# ProPrj_wildCat_2025-03-28.net
KiCad netlist of a schematic drawn in EasyEDA Pro
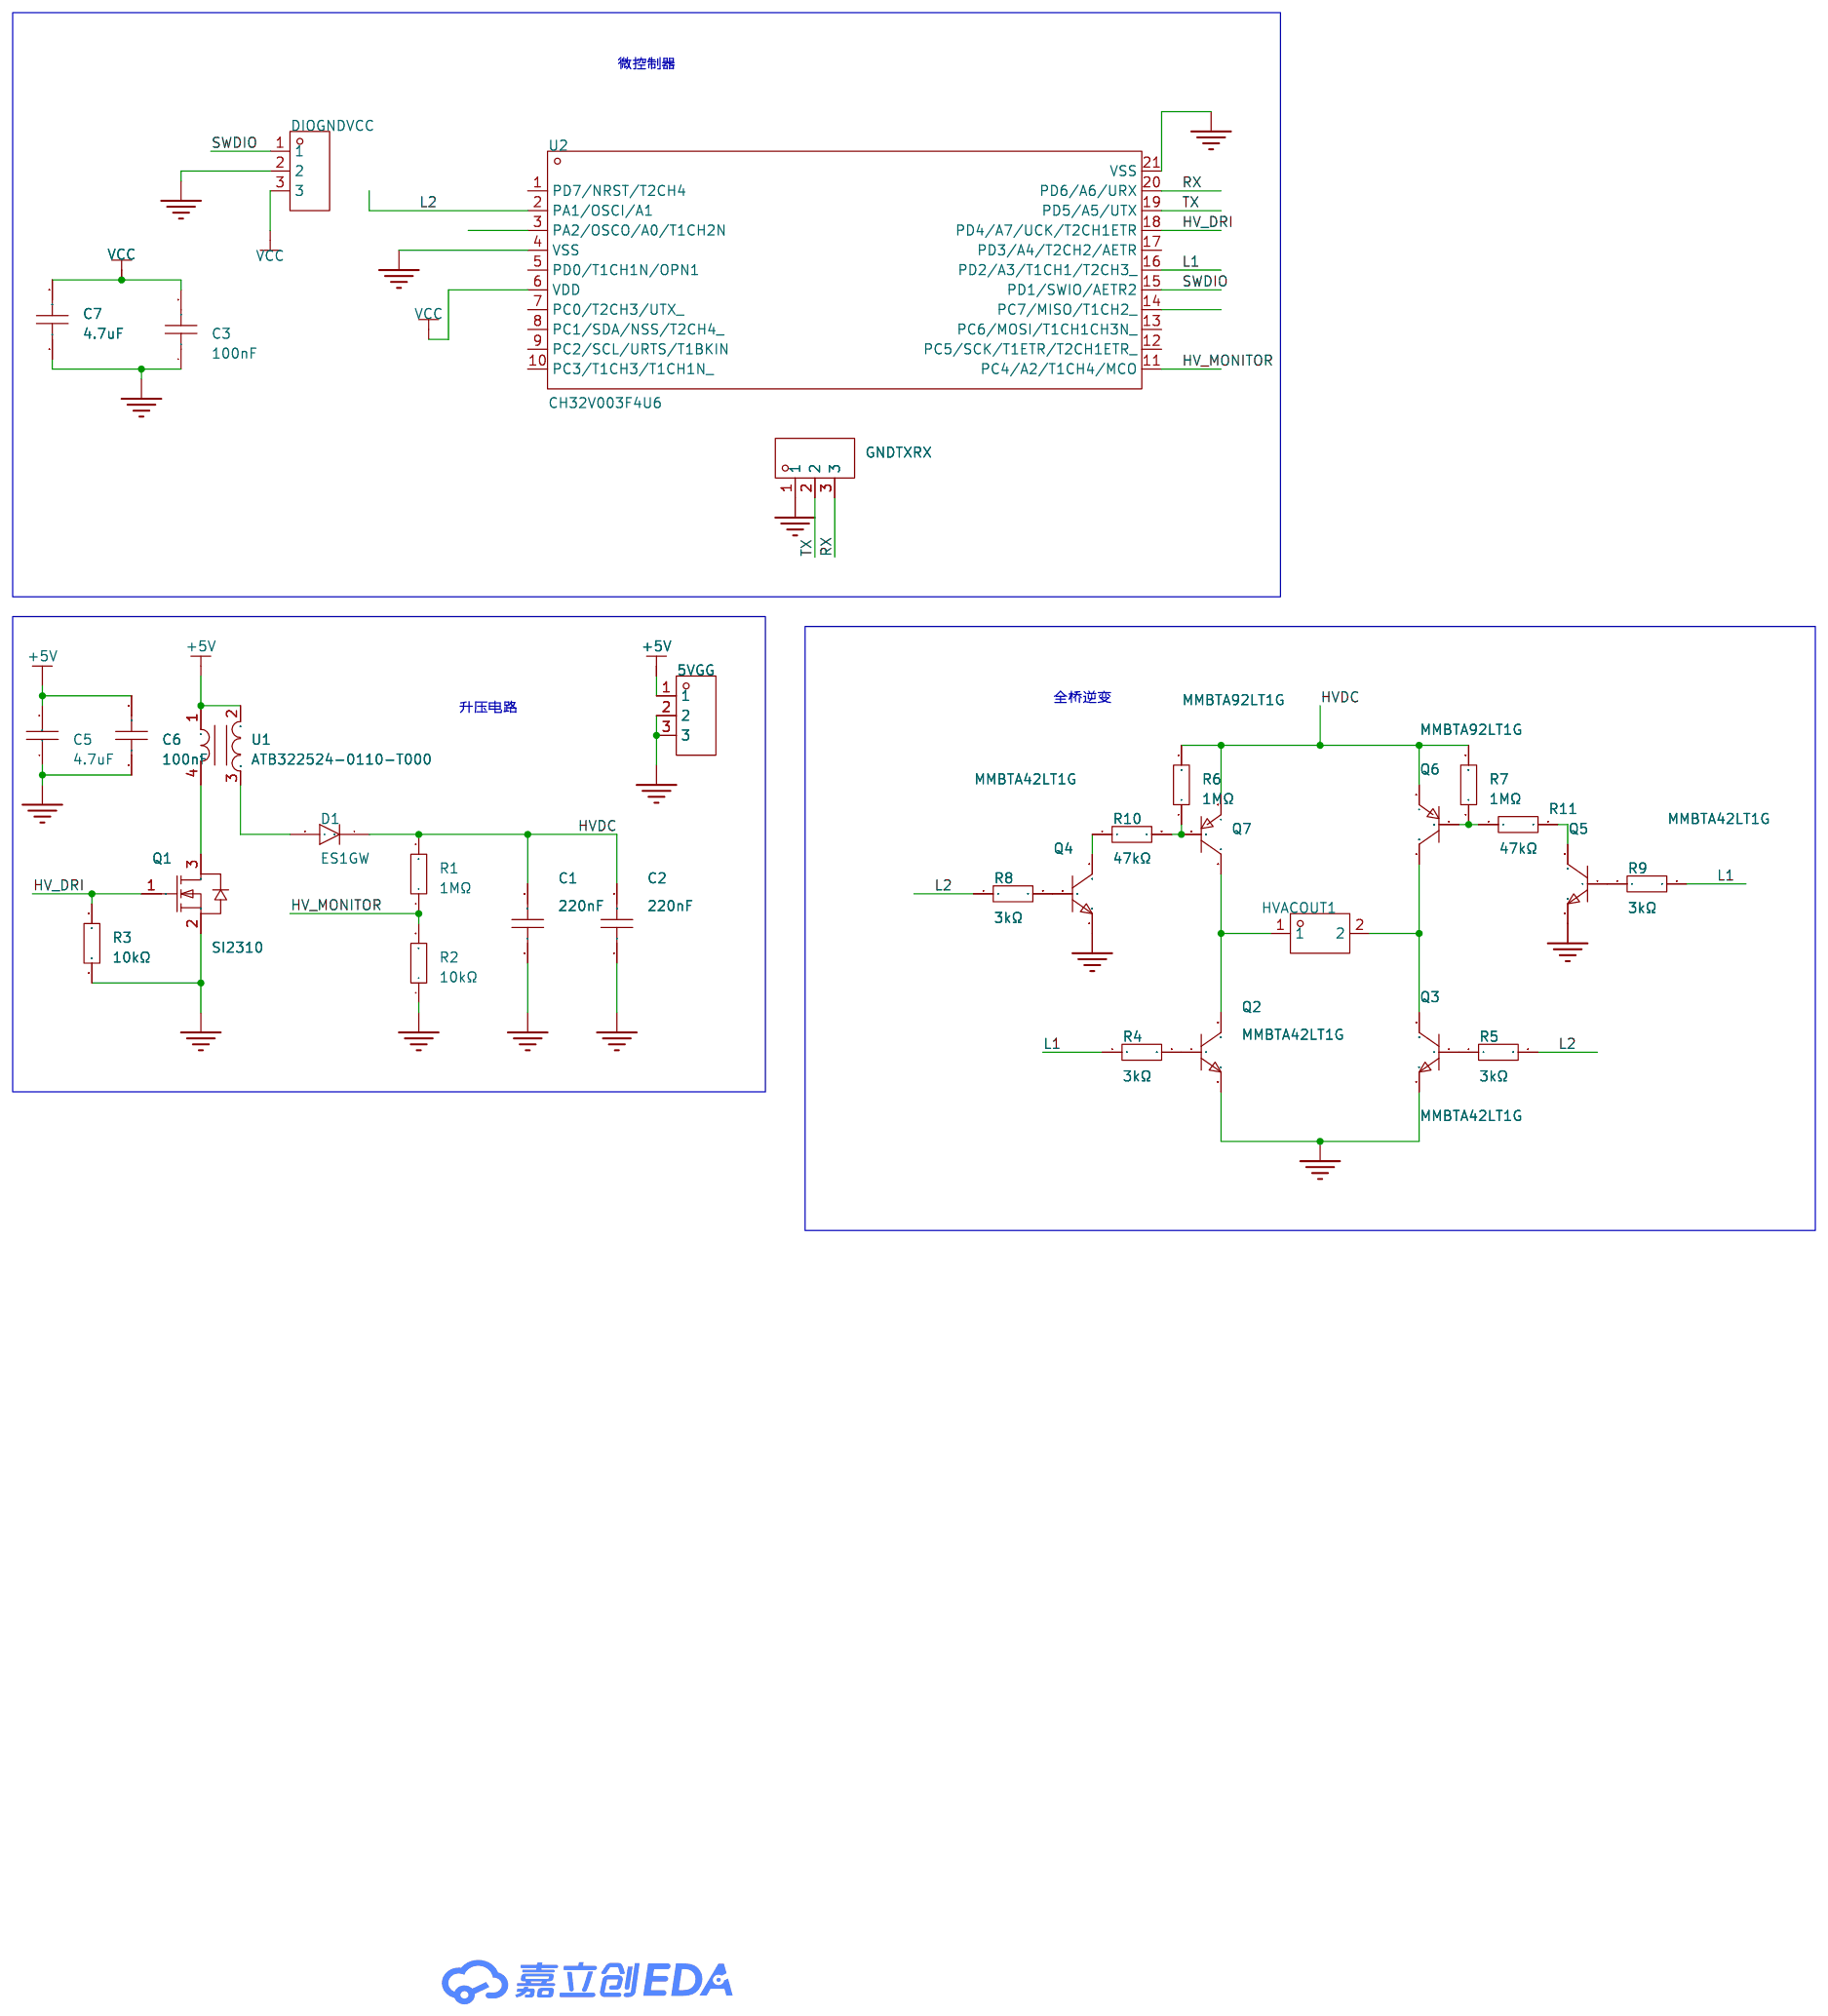
[diagram p0: schematic sheet]

(export (version "E")
  (design (tool "Eeschema 10.0.6"))
  (components
    (comp (ref "5VGG")
      (value "~")
      (footprint "easyedapro:HDR-TH_3P-P2.54-V-F")
      (libsource (lib "easyedapro") (part "PM254V-11-03-H85"))
    )
    (comp (ref "C1")
      (value "220nF")
      (footprint "easyedapro:C1210")
      (description "容值:220nF;精度:±10%;额定电压:250V;材质(温度系数):X7R;")
      (fields
        (field (name "Manufacturer Part") "CC1210KKX7RYBB224")
        (field (name "Manufacturer") "YAGEO(国巨)")
      )
      (libsource (lib "easyedapro") (part "CC1210KKX7RYBB224"))
    )
    (comp (ref "C2")
      (value "220nF")
      (footprint "easyedapro:C1210")
      (description "容值:220nF;精度:±10%;额定电压:250V;材质(温度系数):X7R;")
      (fields
        (field (name "Manufacturer Part") "CC1210KKX7RYBB224")
        (field (name "Manufacturer") "YAGEO(国巨)")
      )
      (libsource (lib "easyedapro") (part "CC1210KKX7RYBB224"))
    )
    (comp (ref "C3")
      (value "100nF")
      (footprint "easyedapro:C0603")
      (description "容值:100nF;精度:±10%;额定电压:50V;温度系数:X7R;")
      (fields
        (field (name "Manufacturer Part") "CGA0603X7R104K500JT")
        (field (name "Manufacturer") "HRE(芯声)")
      )
      (libsource (lib "easyedapro") (part "CGA0603X7R104K500JT"))
    )
    (comp (ref "C5")
      (value "4.7uF")
      (footprint "easyedapro:C0805")
      (description "容值:4.7uF;精度:±10%;额定电压:50V;材质(温度系数):X5R;")
      (fields
        (field (name "Manufacturer Part") "CL21A475KBQNNNE")
        (field (name "Manufacturer") "SAMSUNG(三星)")
      )
      (libsource (lib "easyedapro") (part "CL21A475KBQNNNE"))
    )
    (comp (ref "C6")
      (value "100nF")
      (footprint "easyedapro:C0603")
      (description "容值:100nF;精度:±10%;额定电压:50V;温度系数:X7R;")
      (fields
        (field (name "Manufacturer Part") "CGA0603X7R104K500JT")
        (field (name "Manufacturer") "HRE(芯声)")
      )
      (libsource (lib "easyedapro") (part "CGA0603X7R104K500JT"))
    )
    (comp (ref "C7")
      (value "4.7uF")
      (footprint "easyedapro:C0603")
      (description "容值:4.7uF;精度:±10%;额定电压:16V;材质(温度系数):X5R;")
      (fields
        (field (name "Manufacturer Part") "CL10A475KO8NNNC")
        (field (name "Manufacturer") "SAMSUNG(三星)")
      )
      (libsource (lib "easyedapro") (part "CL10A475KO8NNNC"))
    )
    (comp (ref "D1")
      (value "ES1GW")
      (footprint "easyedapro:SOD-123FL_L2.7-W1.8-LS3.8-RD")
      (description "二极管配置:独立式;正向压降(Vf):1.25V@1A;直流反向耐压(Vr):400V;整流电流:1A;反向恢复时间(trr):35ns;")
      (fields (field (name "Manufacturer") "晶导微电子"))
      (libsource (lib "easyedapro") (part "ES1GW"))
    )
    (comp (ref "DIOGNDVCC")
      (value "~")
      (footprint "easyedapro:HDR-TH_3P-P2.54-V-F")
      (libsource (lib "easyedapro") (part "PM254V-11-03-H85"))
    )
    (comp (ref "GNDTXRX")
      (value "~")
      (footprint "easyedapro:HDR-TH_3P-P2.54-V-F")
      (libsource (lib "easyedapro") (part "PM254V-11-03-H85"))
    )
    (comp (ref "HVACOUT1")
      (value "~")
      (footprint "easyedapro:HDR-TH_2P-P2.54-V-M-2")
      (libsource (lib "easyedapro") (part "HDR-M-2.54_2x1"))
    )
    (comp (ref "Q1")
      (value "SI2310")
      (footprint "easyedapro:SOT-23_L2.9-W1.3-P1.90-LS2.4-BR")
      (description "类型:-;漏源电压(Vdss):60V;连续漏极电流(Id):3A;导通电阻(RDS(on)):125mΩ@4.5V,3A;耗散功率(Pd):1.5W;阈值电压(Vgs(th)):500mV;")
      (fields (field (name "Manufacturer") "GOODWORK(固得沃克)"))
      (libsource (lib "easyedapro") (part "SI2310_C2938374"))
    )
    (comp (ref "Q2")
      (value "MMBTA42LT1G")
      (footprint "easyedapro:SOT-23-3_L2.9-W1.6-P1.90-LS2.8-BR")
      (description "晶体管类型:NPN;集电极电流(Ic):500mA;集射极击穿电压(Vceo):300V;功率(Pd):225mW;直流电流增益(hFE@Ic,Vce):25@10mA,10V;")
      (fields (field (name "Manufacturer") "onsemi(安森美)"))
      (libsource (lib "easyedapro") (part "MMBTA42LT1G"))
    )
    (comp (ref "Q3")
      (value "MMBTA42LT1G")
      (footprint "easyedapro:SOT-23-3_L2.9-W1.6-P1.90-LS2.8-BR")
      (description "晶体管类型:NPN;集电极电流(Ic):500mA;集射极击穿电压(Vceo):300V;功率(Pd):225mW;直流电流增益(hFE@Ic,Vce):25@10mA,10V;")
      (fields (field (name "Manufacturer") "onsemi(安森美)"))
      (libsource (lib "easyedapro") (part "MMBTA42LT1G"))
    )
    (comp (ref "Q4")
      (value "MMBTA42LT1G")
      (footprint "easyedapro:SOT-23-3_L2.9-W1.6-P1.90-LS2.8-BR")
      (description "晶体管类型:NPN;集电极电流(Ic):500mA;集射极击穿电压(Vceo):300V;功率(Pd):225mW;直流电流增益(hFE@Ic,Vce):25@10mA,10V;")
      (fields (field (name "Manufacturer") "onsemi(安森美)"))
      (libsource (lib "easyedapro") (part "MMBTA42LT1G"))
    )
    (comp (ref "Q5")
      (value "MMBTA42LT1G")
      (footprint "easyedapro:SOT-23-3_L2.9-W1.6-P1.90-LS2.8-BR")
      (description "晶体管类型:NPN;集电极电流(Ic):500mA;集射极击穿电压(Vceo):300V;功率(Pd):225mW;直流电流增益(hFE@Ic,Vce):25@10mA,10V;")
      (fields (field (name "Manufacturer") "onsemi(安森美)"))
      (libsource (lib "easyedapro") (part "MMBTA42LT1G"))
    )
    (comp (ref "Q6")
      (value "MMBTA92LT1G")
      (footprint "easyedapro:SOT-23-3_L2.9-W1.6-P1.90-LS2.8-BR")
      (description "晶体管类型:PNP;集电极电流(Ic):500mA;集射极击穿电压(Vceo):300V;功率(Pd):225mW;直流电流增益(hFE@Ic,Vce):25@1.0mA,10V;")
      (fields (field (name "Manufacturer") "onsemi(安森美)"))
      (libsource (lib "easyedapro") (part "MMBTA92LT1G"))
    )
    (comp (ref "Q7")
      (value "MMBTA92LT1G")
      (footprint "easyedapro:SOT-23-3_L2.9-W1.6-P1.90-LS2.8-BR")
      (description "晶体管类型:PNP;集电极电流(Ic):500mA;集射极击穿电压(Vceo):300V;功率(Pd):225mW;直流电流增益(hFE@Ic,Vce):25@1.0mA,10V;")
      (fields (field (name "Manufacturer") "onsemi(安森美)"))
      (libsource (lib "easyedapro") (part "MMBTA92LT1G"))
    )
    (comp (ref "R1")
      (value "1MΩ")
      (footprint "easyedapro:R0603")
      (description "电阻类型:厚膜电阻;阻值:1MΩ;精度:±1%;功率:100mW;最大工作电压:75V;温度系数:±100ppm/°C;")
      (fields
        (field (name "Manufacturer Part") "0402WGF1004TCE")
        (field (name "Manufacturer") "UNI-ROYAL(厚声)")
      )
      (libsource (lib "easyedapro") (part "0603WAF1004T5E"))
    )
    (comp (ref "R2")
      (value "10kΩ")
      (footprint "easyedapro:R0402")
      (description "电阻类型:厚膜电阻;阻值:10kΩ;精度:±1%;功率:62.5mW;最大工作电压:50V;温度系数:±100ppm/°C;")
      (fields
        (field (name "Manufacturer Part") "0402WGF1002TCE")
        (field (name "Manufacturer") "UNI-ROYAL(厚声)")
      )
      (libsource (lib "easyedapro") (part "0402WGF1002TCE"))
    )
    (comp (ref "R3")
      (value "10kΩ")
      (footprint "easyedapro:R0402")
      (description "电阻类型:厚膜电阻;阻值:10kΩ;精度:±1%;功率:62.5mW;最大工作电压:50V;温度系数:±100ppm/°C;")
      (fields
        (field (name "Manufacturer Part") "0402WGF1002TCE")
        (field (name "Manufacturer") "UNI-ROYAL(厚声)")
      )
      (libsource (lib "easyedapro") (part "0402WGF1002TCE"))
    )
    (comp (ref "R4")
      (value "3kΩ")
      (footprint "easyedapro:R0603")
      (description "电阻类型:厚膜电阻;阻值:3kΩ;精度:±1%;功率:100mW;最大工作电压:75V;温度系数:±100ppm/°C;")
      (fields (field (name "Manufacturer Part") "FRC0402F3001TS") (field (name "Manufacturer") "FOJAN(富捷)"))
      (libsource (lib "easyedapro") (part "0603WAF3001T5E"))
    )
    (comp (ref "R5")
      (value "3kΩ")
      (footprint "easyedapro:R0603")
      (description "电阻类型:厚膜电阻;阻值:3kΩ;精度:±1%;功率:100mW;最大工作电压:75V;温度系数:±100ppm/°C;")
      (fields (field (name "Manufacturer Part") "FRC0402F3001TS") (field (name "Manufacturer") "FOJAN(富捷)"))
      (libsource (lib "easyedapro") (part "0603WAF3001T5E"))
    )
    (comp (ref "R6")
      (value "1MΩ")
      (footprint "easyedapro:R0603")
      (description "电阻类型:厚膜电阻;阻值:1MΩ;精度:±1%;功率:100mW;最大工作电压:75V;温度系数:±100ppm/°C;")
      (fields
        (field (name "Manufacturer Part") "0402WGF1004TCE")
        (field (name "Manufacturer") "UNI-ROYAL(厚声)")
      )
      (libsource (lib "easyedapro") (part "0603WAF1004T5E"))
    )
    (comp (ref "R7")
      (value "1MΩ")
      (footprint "easyedapro:R0603")
      (description "电阻类型:厚膜电阻;阻值:1MΩ;精度:±1%;功率:100mW;最大工作电压:75V;温度系数:±100ppm/°C;")
      (fields
        (field (name "Manufacturer Part") "0402WGF1004TCE")
        (field (name "Manufacturer") "UNI-ROYAL(厚声)")
      )
      (libsource (lib "easyedapro") (part "0603WAF1004T5E"))
    )
    (comp (ref "R8")
      (value "3kΩ")
      (footprint "easyedapro:R0603")
      (description "电阻类型:厚膜电阻;阻值:3kΩ;精度:±1%;功率:100mW;最大工作电压:75V;温度系数:±100ppm/°C;")
      (fields (field (name "Manufacturer Part") "FRC0402F3001TS") (field (name "Manufacturer") "FOJAN(富捷)"))
      (libsource (lib "easyedapro") (part "0603WAF3001T5E"))
    )
    (comp (ref "R9")
      (value "3kΩ")
      (footprint "easyedapro:R0603")
      (description "电阻类型:厚膜电阻;阻值:3kΩ;精度:±1%;功率:100mW;最大工作电压:75V;温度系数:±100ppm/°C;")
      (fields (field (name "Manufacturer Part") "FRC0402F3001TS") (field (name "Manufacturer") "FOJAN(富捷)"))
      (libsource (lib "easyedapro") (part "0603WAF3001T5E"))
    )
    (comp (ref "R10")
      (value "47kΩ")
      (footprint "easyedapro:R0603")
      (description "电阻类型:厚膜电阻;阻值:47kΩ;精度:±1%;功率:100mW;最大工作电压:75V;温度系数:±100ppm/°C;")
      (fields
        (field (name "Manufacturer Part") "0402WGF4702TCE")
        (field (name "Manufacturer") "UNI-ROYAL(厚声)")
      )
      (libsource (lib "easyedapro") (part "0603WAF4702T5E"))
    )
    (comp (ref "R11")
      (value "47kΩ")
      (footprint "easyedapro:R0603")
      (description "电阻类型:厚膜电阻;阻值:47kΩ;精度:±1%;功率:100mW;最大工作电压:75V;温度系数:±100ppm/°C;")
      (fields
        (field (name "Manufacturer Part") "0402WGF4702TCE")
        (field (name "Manufacturer") "UNI-ROYAL(厚声)")
      )
      (libsource (lib "easyedapro") (part "0603WAF4702T5E"))
    )
    (comp (ref "U1")
      (value "ATB322524-0110-T000")
      (footprint "easyedapro:XFMR-SMD_ATB322515-0110-T000")
      (description "初级电压:-;次级电压:-;输出电流:-;功率:-;")
      (fields (field (name "Manufacturer") "TDK"))
      (libsource (lib "easyedapro") (part "ATB322524-0110-T000"))
    )
    (comp (ref "U2")
      (value "CH32V003F4U6")
      (footprint "easyedapro:QFN-20_L3.0-W3.0-P0.40-TL-EP1.7")
      (description "CPU内核:RISC-V;程序存储容量:16KB;RAM总容量:2KB;GPIO端口数量:18;工作电压范围:-;CPU最大主频:48MHz;程序存储器类型:-;应用领域:-;")
      (fields (field (name "Manufacturer") "WCH(南京沁恒)"))
      (libsource (lib "easyedapro") (part "CH32V003F4U6"))
    )
  )
  (nets
    (net (code "1") (name "+5V") (class "Default")
      (node (ref "5VGG") (pin "1") (pinfunction "1_1") (pintype "unspecified"))
      (node (ref "C5") (pin "2") (pinfunction "2_2") (pintype "input"))
      (node (ref "C6") (pin "2") (pinfunction "2_2") (pintype "unspecified"))
      (node (ref "U1") (pin "1") (pinfunction "1_1") (pintype "unspecified"))
      (node (ref "U1") (pin "2") (pinfunction "2_2") (pintype "unspecified"))
    )
    (net (code "2") (name "/HVDC") (class "Default")
      (node (ref "C1") (pin "2") (pinfunction "2_2") (pintype "unspecified"))
      (node (ref "C2") (pin "2") (pinfunction "2_2") (pintype "unspecified"))
      (node (ref "D1") (pin "1") (pinfunction "C_1") (pintype "unspecified"))
      (node (ref "Q6") (pin "2") (pinfunction "E_2") (pintype "unspecified"))
      (node (ref "Q7") (pin "2") (pinfunction "E_2") (pintype "unspecified"))
      (node (ref "R1") (pin "2") (pinfunction "2_2") (pintype "input"))
      (node (ref "R6") (pin "2") (pinfunction "2_2") (pintype "input"))
      (node (ref "R7") (pin "2") (pinfunction "2_2") (pintype "input"))
    )
    (net (code "3") (name "/HV_DRI") (class "Default")
      (node (ref "Q1") (pin "1") (pinfunction "G_1") (pintype "unspecified"))
      (node (ref "R3") (pin "2") (pinfunction "2_2") (pintype "input"))
      (node (ref "U2") (pin "18") (pinfunction "PD4/A7/UCK/T2CH1ETR_18") (pintype "unspecified"))
    )
    (net (code "4") (name "/HV_MONITOR") (class "Default")
      (node (ref "R1") (pin "1") (pinfunction "1_1") (pintype "input"))
      (node (ref "R2") (pin "2") (pinfunction "2_2") (pintype "input"))
      (node (ref "U2") (pin "11") (pinfunction "PC4/A2/T1CH4/MCO_11") (pintype "unspecified"))
    )
    (net (code "5") (name "/L1") (class "Default")
      (node (ref "R4") (pin "1") (pinfunction "1_1") (pintype "input"))
      (node (ref "R9") (pin "2") (pinfunction "2_2") (pintype "input"))
      (node (ref "U2") (pin "16") (pinfunction "PD2/A3/T1CH1/T2CH3__16") (pintype "unspecified"))
    )
    (net (code "6") (name "/L2") (class "Default")
      (node (ref "R5") (pin "2") (pinfunction "2_2") (pintype "input"))
      (node (ref "R8") (pin "1") (pinfunction "1_1") (pintype "input"))
      (node (ref "U2") (pin "2") (pinfunction "PA1/OSCI/A1_2") (pintype "unspecified"))
    )
    (net (code "7") (name "/RX") (class "Default")
      (node (ref "GNDTXRX") (pin "3") (pinfunction "3_3") (pintype "unspecified"))
      (node (ref "U2") (pin "20") (pinfunction "PD6/A6/URX_20") (pintype "unspecified"))
    )
    (net (code "8") (name "/SWDIO") (class "Default")
      (node (ref "DIOGNDVCC") (pin "1") (pinfunction "1_1") (pintype "unspecified"))
      (node (ref "U2") (pin "15") (pinfunction "PD1/SWIO/AETR2_15") (pintype "unspecified"))
    )
    (net (code "9") (name "/TX") (class "Default")
      (node (ref "GNDTXRX") (pin "2") (pinfunction "2_2") (pintype "unspecified"))
      (node (ref "U2") (pin "19") (pinfunction "PD5/A5/UTX_19") (pintype "unspecified"))
    )
    (net (code "10") (name "GND") (class "Default")
      (node (ref "5VGG") (pin "2") (pinfunction "2_2") (pintype "unspecified"))
      (node (ref "5VGG") (pin "3") (pinfunction "3_3") (pintype "unspecified"))
      (node (ref "C1") (pin "1") (pinfunction "1_1") (pintype "unspecified"))
      (node (ref "C2") (pin "1") (pinfunction "1_1") (pintype "unspecified"))
      (node (ref "C3") (pin "1") (pinfunction "1_1") (pintype "unspecified"))
      (node (ref "C5") (pin "1") (pinfunction "1_1") (pintype "input"))
      (node (ref "C6") (pin "1") (pinfunction "1_1") (pintype "unspecified"))
      (node (ref "C7") (pin "1") (pinfunction "1_1") (pintype "unspecified"))
      (node (ref "DIOGNDVCC") (pin "2") (pinfunction "2_2") (pintype "unspecified"))
      (node (ref "GNDTXRX") (pin "1") (pinfunction "1_1") (pintype "unspecified"))
      (node (ref "Q1") (pin "2") (pinfunction "S_2") (pintype "unspecified"))
      (node (ref "Q2") (pin "2") (pinfunction "2_2") (pintype "input"))
      (node (ref "Q3") (pin "2") (pinfunction "2_2") (pintype "input"))
      (node (ref "Q4") (pin "2") (pinfunction "2_2") (pintype "input"))
      (node (ref "Q5") (pin "2") (pinfunction "2_2") (pintype "input"))
      (node (ref "R2") (pin "1") (pinfunction "1_1") (pintype "input"))
      (node (ref "R3") (pin "1") (pinfunction "1_1") (pintype "input"))
      (node (ref "U2") (pin "21") (pinfunction "VSS_21") (pintype "unspecified"))
      (node (ref "U2") (pin "4") (pinfunction "VSS_4") (pintype "unspecified"))
    )
    (net (code "11") (name "Net-(D1-A)") (class "Default")
      (node (ref "D1") (pin "2") (pinfunction "A_2") (pintype "unspecified"))
      (node (ref "U1") (pin "3") (pinfunction "3_3") (pintype "unspecified"))
    )
    (net (code "12") (name "Net-(Q1-D)") (class "Default")
      (node (ref "Q1") (pin "3") (pinfunction "D_3") (pintype "unspecified"))
      (node (ref "U1") (pin "4") (pinfunction "4_4") (pintype "unspecified"))
    )
    (net (code "13") (name "Net-(Q2-Pad1)") (class "Default")
      (node (ref "Q2") (pin "1") (pinfunction "1_1") (pintype "input"))
      (node (ref "R4") (pin "2") (pinfunction "2_2") (pintype "input"))
    )
    (net (code "14") (name "Net-(Q3-Pad1)") (class "Default")
      (node (ref "Q3") (pin "1") (pinfunction "1_1") (pintype "input"))
      (node (ref "R5") (pin "1") (pinfunction "1_1") (pintype "input"))
    )
    (net (code "15") (name "Net-(Q4-Pad1)") (class "Default")
      (node (ref "Q4") (pin "1") (pinfunction "1_1") (pintype "input"))
      (node (ref "R8") (pin "2") (pinfunction "2_2") (pintype "input"))
    )
    (net (code "16") (name "Net-(Q4-Pad3)") (class "Default")
      (node (ref "Q4") (pin "3") (pinfunction "3_3") (pintype "input"))
      (node (ref "R10") (pin "1") (pinfunction "1_1") (pintype "input"))
    )
    (net (code "17") (name "Net-(Q5-Pad1)") (class "Default")
      (node (ref "Q5") (pin "1") (pinfunction "1_1") (pintype "input"))
      (node (ref "R9") (pin "1") (pinfunction "1_1") (pintype "input"))
    )
    (net (code "18") (name "Net-(Q5-Pad3)") (class "Default")
      (node (ref "Q5") (pin "3") (pinfunction "3_3") (pintype "input"))
      (node (ref "R11") (pin "2") (pinfunction "2_2") (pintype "input"))
    )
    (net (code "19") (name "Net-(Q6-B)") (class "Default")
      (node (ref "Q6") (pin "1") (pinfunction "B_1") (pintype "unspecified"))
      (node (ref "R11") (pin "1") (pinfunction "1_1") (pintype "input"))
      (node (ref "R7") (pin "1") (pinfunction "1_1") (pintype "input"))
    )
    (net (code "20") (name "Net-(Q6-C)") (class "Default")
      (node (ref "HVACOUT1") (pin "2") (pinfunction "2_2") (pintype "input"))
      (node (ref "Q3") (pin "3") (pinfunction "3_3") (pintype "input"))
      (node (ref "Q6") (pin "3") (pinfunction "C_3") (pintype "unspecified"))
    )
    (net (code "21") (name "Net-(Q7-B)") (class "Default")
      (node (ref "Q7") (pin "1") (pinfunction "B_1") (pintype "unspecified"))
      (node (ref "R10") (pin "2") (pinfunction "2_2") (pintype "input"))
      (node (ref "R6") (pin "1") (pinfunction "1_1") (pintype "input"))
    )
    (net (code "22") (name "Net-(Q7-C)") (class "Default")
      (node (ref "HVACOUT1") (pin "1") (pinfunction "1_1") (pintype "input"))
      (node (ref "Q2") (pin "3") (pinfunction "3_3") (pintype "input"))
      (node (ref "Q7") (pin "3") (pinfunction "C_3") (pintype "unspecified"))
    )
    (net (code "23") (name "VCC") (class "Default")
      (node (ref "C3") (pin "2") (pinfunction "2_2") (pintype "unspecified"))
      (node (ref "C7") (pin "2") (pinfunction "2_2") (pintype "unspecified"))
      (node (ref "DIOGNDVCC") (pin "3") (pinfunction "3_3") (pintype "unspecified"))
      (node (ref "U2") (pin "6") (pinfunction "VDD_6") (pintype "unspecified"))
    )
    (net (code "24") (name "unconnected-(U2-PA2{slash}OSCO{slash}A0{slash}T1CH2N-Pad3)") (class "Default")
      (node (ref "U2") (pin "3") (pinfunction "PA2/OSCO/A0/T1CH2N_3") (pintype "unspecified"))
    )
    (net (code "25") (name "unconnected-(U2-PC0{slash}T2CH3{slash}UTX_-Pad7)") (class "Default")
      (node (ref "U2") (pin "7") (pinfunction "PC0/T2CH3/UTX__7") (pintype "unspecified"))
    )
    (net (code "26") (name "unconnected-(U2-PC1{slash}SDA{slash}NSS{slash}T2CH4_-Pad8)") (class "Default")
      (node (ref "U2") (pin "8") (pinfunction "PC1/SDA/NSS/T2CH4__8") (pintype "unspecified"))
    )
    (net (code "27") (name "unconnected-(U2-PC2{slash}SCL{slash}URTS{slash}T1BKIN-Pad9)") (class "Default")
      (node (ref "U2") (pin "9") (pinfunction "PC2/SCL/URTS/T1BKIN_9") (pintype "unspecified"))
    )
    (net (code "28") (name "unconnected-(U2-PC3{slash}T1CH3{slash}T1CH1N_-Pad10)") (class "Default")
      (node (ref "U2") (pin "10") (pinfunction "PC3/T1CH3/T1CH1N__10") (pintype "unspecified"))
    )
    (net (code "29") (name "unconnected-(U2-PC5{slash}SCK{slash}T1ETR{slash}T2CH1ETR_-Pad12)") (class "Default")
      (node (ref "U2") (pin "12") (pinfunction "PC5/SCK/T1ETR/T2CH1ETR__12") (pintype "unspecified"))
    )
    (net (code "30") (name "unconnected-(U2-PC6{slash}MOSI{slash}T1CH1CH3N_-Pad13)") (class "Default")
      (node (ref "U2") (pin "13") (pinfunction "PC6/MOSI/T1CH1CH3N__13") (pintype "unspecified"))
    )
    (net (code "31") (name "unconnected-(U2-PC7{slash}MISO{slash}T1CH2_-Pad14)") (class "Default")
      (node (ref "U2") (pin "14") (pinfunction "PC7/MISO/T1CH2__14") (pintype "unspecified"))
    )
    (net (code "32") (name "unconnected-(U2-PD0{slash}T1CH1N{slash}OPN1-Pad5)") (class "Default")
      (node (ref "U2") (pin "5") (pinfunction "PD0/T1CH1N/OPN1_5") (pintype "unspecified"))
    )
    (net (code "33") (name "unconnected-(U2-PD3{slash}A4{slash}T2CH2{slash}AETR-Pad17)") (class "Default")
      (node (ref "U2") (pin "17") (pinfunction "PD3/A4/T2CH2/AETR_17") (pintype "unspecified"))
    )
    (net (code "34") (name "unconnected-(U2-PD7{slash}NRST{slash}T2CH4-Pad1)") (class "Default")
      (node (ref "U2") (pin "1") (pinfunction "PD7/NRST/T2CH4_1") (pintype "unspecified"))
    )
  )
)
